# CCM0006.net
KiCad netlist of a schematic drawn in EAGLE
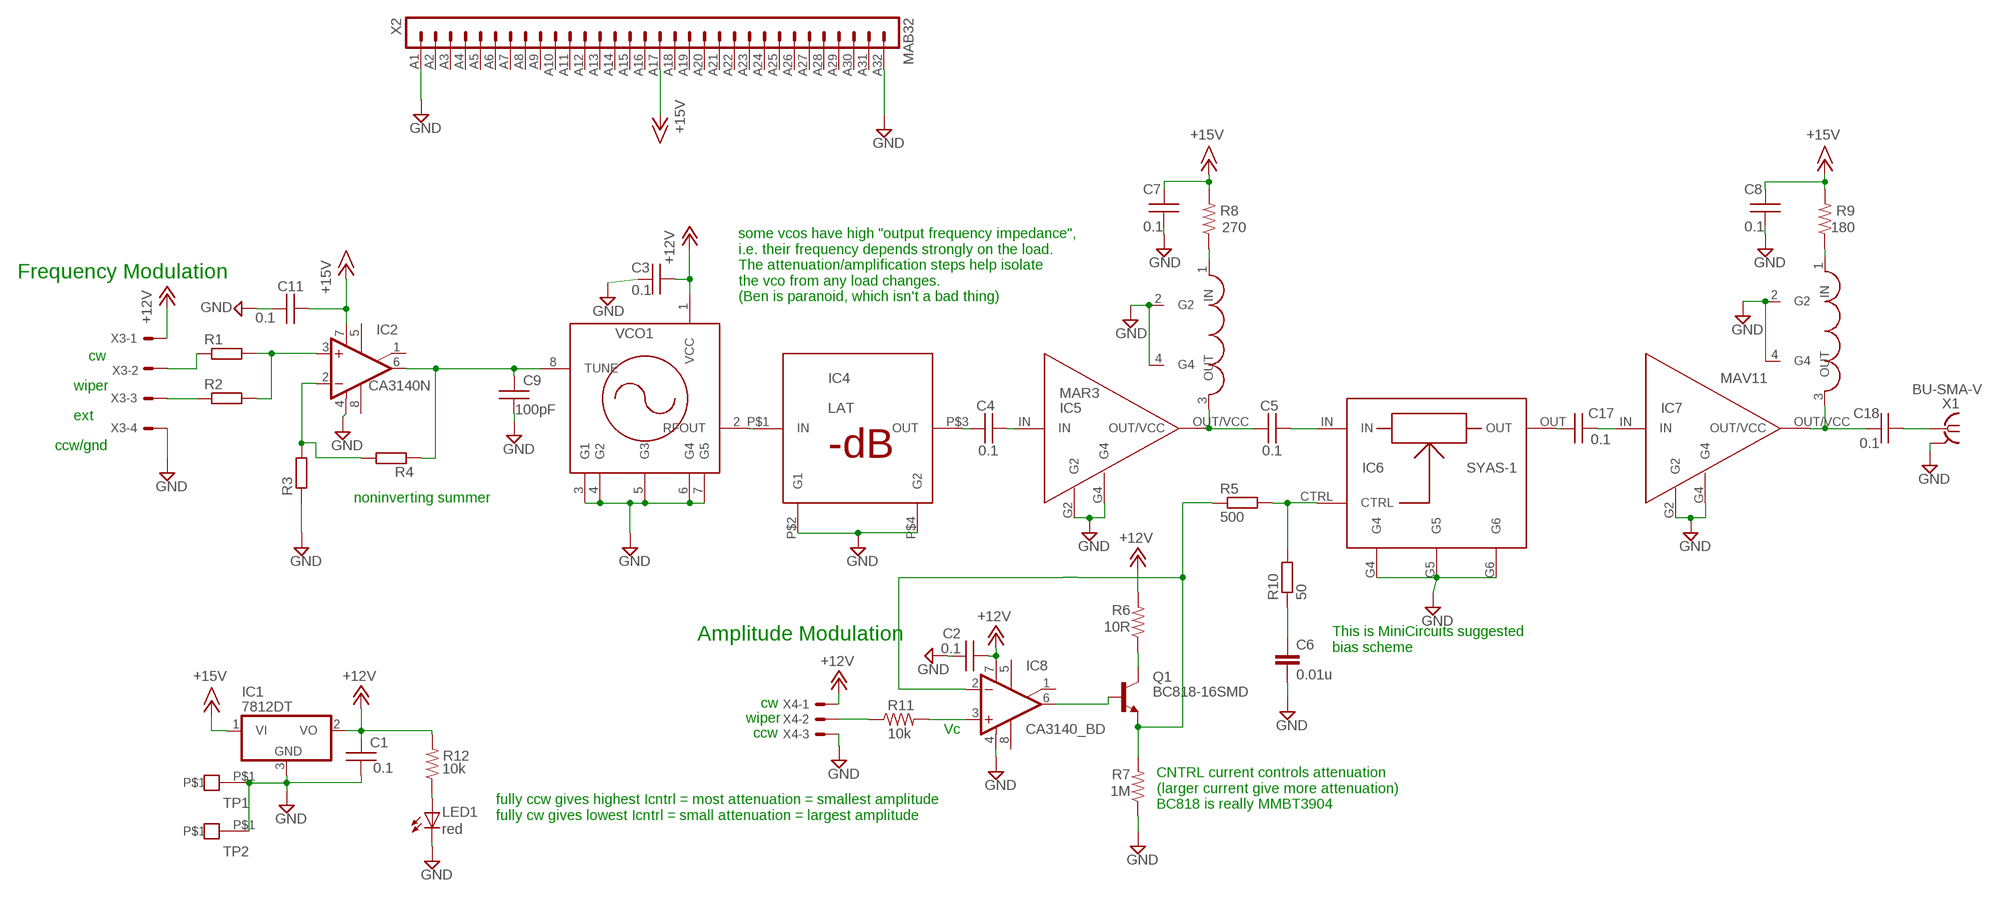
[diagram p0: schematic, sheet 1]

(export (version "E")
  (design (tool "Eeschema 10.0.6"))
  (components
    (comp (ref "C1")
      (value "0.1")
      (footprint "eagle-import:0805")
      (libsource (lib "eagle-import") (part "CAPACITOR0805"))
    )
    (comp (ref "C2")
      (value "0.1")
      (footprint "eagle-import:0805")
      (libsource (lib "eagle-import") (part "CAPACITOR0805"))
    )
    (comp (ref "C3")
      (value "0.1")
      (footprint "eagle-import:0805")
      (libsource (lib "eagle-import") (part "CAPACITOR0805"))
    )
    (comp (ref "C4")
      (value "0.1")
      (footprint "eagle-import:2010")
      (libsource (lib "eagle-import") (part "CAPACITOR2010"))
    )
    (comp (ref "C5")
      (value "0.1")
      (footprint "eagle-import:2010")
      (libsource (lib "eagle-import") (part "CAPACITOR2010"))
    )
    (comp (ref "C6")
      (value "0.01u")
      (footprint "eagle-import:C0805")
      (libsource (lib "eagle-import") (part "C-EUC0805"))
    )
    (comp (ref "C7")
      (value "0.1")
      (footprint "eagle-import:0805")
      (libsource (lib "eagle-import") (part "CAPACITOR0805"))
    )
    (comp (ref "C8")
      (value "0.1")
      (footprint "eagle-import:0603")
      (libsource (lib "eagle-import") (part "CAPACITOR0603"))
    )
    (comp (ref "C9")
      (value "100pF")
      (footprint "eagle-import:0805")
      (libsource (lib "eagle-import") (part "CAPACITOR0805"))
    )
    (comp (ref "C11")
      (value "0.1")
      (footprint "eagle-import:0805")
      (libsource (lib "eagle-import") (part "CAPACITOR0805"))
    )
    (comp (ref "C17")
      (value "0.1")
      (footprint "eagle-import:2010")
      (libsource (lib "eagle-import") (part "CAPACITOR2010"))
    )
    (comp (ref "C18")
      (value "0.1")
      (footprint "eagle-import:2010")
      (libsource (lib "eagle-import") (part "CAPACITOR2010"))
    )
    (comp (ref "IC1")
      (value "7812DT")
      (footprint "eagle-import:TO252")
      (libsource (lib "eagle-import") (part "78DT12"))
    )
    (comp (ref "IC2")
      (value "CA3140N")
      (footprint "eagle-import:DIL08")
      (libsource (lib "eagle-import") (part "CA3140N"))
    )
    (comp (ref "IC4")
      (value "LAT")
      (footprint "eagle-import:MMM168")
      (libsource (lib "eagle-import") (part "LAT"))
    )
    (comp (ref "IC5")
      (value "MAR3")
      (footprint "eagle-import:MAR")
      (libsource (lib "eagle-import") (part "MAR3"))
    )
    (comp (ref "IC6")
      (value "SYAS-1")
      (footprint "eagle-import:TTT166")
      (libsource (lib "eagle-import") (part "SYAS-1"))
    )
    (comp (ref "IC7")
      (value "MAV11")
      (footprint "eagle-import:MAR")
      (libsource (lib "eagle-import") (part "MAV11"))
    )
    (comp (ref "IC8")
      (value "CA3140_BD")
      (footprint "eagle-import:SO08")
      (libsource (lib "eagle-import") (part "CA3140_BD"))
    )
    (comp (ref "L1")
      (value "TCCH-80")
      (footprint "eagle-import:PL-147")
      (libsource (lib "eagle-import") (part "TCCH-80"))
    )
    (comp (ref "L2")
      (value "TCCH-80")
      (footprint "eagle-import:PL-147")
      (libsource (lib "eagle-import") (part "TCCH-80"))
    )
    (comp (ref "LED1")
      (value "red")
      (footprint "eagle-import:CHIPLED_0603")
      (libsource (lib "eagle-import") (part "LEDCHIPLED_0603"))
    )
    (comp (ref "Q1")
      (value "BC818-16SMD")
      (footprint "eagle-import:SOT23-BEC")
      (libsource (lib "eagle-import") (part "BC818SMD-16"))
    )
    (comp (ref "R1")
      (value "R-EU_0204/7")
      (footprint "eagle-import:0204_7")
      (libsource (lib "eagle-import") (part "R-EU_0204/7"))
    )
    (comp (ref "R2")
      (value "R-EU_0204/7")
      (footprint "eagle-import:0204_7")
      (libsource (lib "eagle-import") (part "R-EU_0204/7"))
    )
    (comp (ref "R3")
      (value "R-EU_0204/7")
      (footprint "eagle-import:0204_7")
      (libsource (lib "eagle-import") (part "R-EU_0204/7"))
    )
    (comp (ref "R4")
      (value "R-EU_0204/7")
      (footprint "eagle-import:0204_7")
      (libsource (lib "eagle-import") (part "R-EU_0204/7"))
    )
    (comp (ref "R5")
      (value "500")
      (footprint "eagle-import:R0805")
      (libsource (lib "eagle-import") (part "R-EU_R0805"))
    )
    (comp (ref "R6")
      (value "10R")
      (footprint "eagle-import:0805")
      (libsource (lib "eagle-import") (part "RESISTOR0805"))
    )
    (comp (ref "R7")
      (value "1M")
      (footprint "eagle-import:0805")
      (libsource (lib "eagle-import") (part "RESISTOR0805"))
    )
    (comp (ref "R8")
      (value "270")
      (footprint "eagle-import:2010")
      (libsource (lib "eagle-import") (part "RESISTOR2010"))
    )
    (comp (ref "R9")
      (value "180")
      (footprint "eagle-import:2010")
      (libsource (lib "eagle-import") (part "RESISTOR2010"))
    )
    (comp (ref "R10")
      (value "50")
      (footprint "eagle-import:R0805")
      (libsource (lib "eagle-import") (part "R-EU_R0805"))
    )
    (comp (ref "R11")
      (value "10k")
      (footprint "eagle-import:0805")
      (libsource (lib "eagle-import") (part "RESISTOR0805"))
    )
    (comp (ref "R12")
      (value "10k")
      (footprint "eagle-import:0805")
      (libsource (lib "eagle-import") (part "RESISTOR0805"))
    )
    (comp (ref "TP1")
      (value "TESTPOINT")
      (footprint "eagle-import:TESTPOINT")
      (libsource (lib "eagle-import") (part "TESTPOINT"))
    )
    (comp (ref "TP2")
      (value "TESTPOINT")
      (footprint "eagle-import:TESTPOINT")
      (libsource (lib "eagle-import") (part "TESTPOINT"))
    )
    (comp (ref "VCO1")
      (value "POSBIGPAD")
      (footprint "eagle-import:A01BIDPAD")
      (libsource (lib "eagle-import") (part "POSBIGPAD"))
    )
    (comp (ref "X1")
      (value "BU-SMA-V")
      (footprint "eagle-import:BU-SMA-V")
      (libsource (lib "eagle-import") (part "BU-SMA-V"))
    )
    (comp (ref "X2")
      (value "MAB32")
      (footprint "eagle-import:MAB32")
      (libsource (lib "eagle-import") (part "MAB32"))
    )
    (comp (ref "X3")
      (value "22-23-2041")
      (footprint "eagle-import:22-23-2041")
      (fields (field (name "MF") "MOLEX"))
      (libsource (lib "eagle-import") (part "22-23-2041"))
    )
    (comp (ref "X4")
      (value "22-23-2031")
      (footprint "eagle-import:22-23-2031")
      (fields (field (name "MF") "MOLEX"))
      (libsource (lib "eagle-import") (part "22-23-2031"))
    )
  )
  (nets
    (net (code "1") (name "+12V") (class "Default")
      (node (ref "C1") (pin "1") (pinfunction "1_1") (pintype "passive"))
      (node (ref "C2") (pin "2") (pinfunction "2_2") (pintype "passive"))
      (node (ref "C3") (pin "1") (pinfunction "1_1") (pintype "passive"))
      (node (ref "IC1") (pin "2") (pinfunction "VO_2") (pintype "passive"))
      (node (ref "IC8") (pin "7") (pinfunction "V+_7") (pintype "power_in"))
      (node (ref "R12") (pin "2") (pinfunction "2_2") (pintype "passive"))
      (node (ref "R6") (pin "2") (pinfunction "2_2") (pintype "passive"))
      (node (ref "VCO1") (pin "1") (pinfunction "VCC_1") (pintype "input"))
      (node (ref "X3") (pin "1") (pinfunction "S_1") (pintype "passive"))
      (node (ref "X4") (pin "1") (pinfunction "S_1") (pintype "passive"))
    )
    (net (code "2") (name "+15V") (class "Default")
      (node (ref "C11") (pin "2") (pinfunction "2_2") (pintype "passive"))
      (node (ref "C7") (pin "1") (pinfunction "1_1") (pintype "passive"))
      (node (ref "C8") (pin "1") (pinfunction "1_1") (pintype "passive"))
      (node (ref "IC1") (pin "1") (pinfunction "VI_1") (pintype "input"))
      (node (ref "IC2") (pin "7") (pinfunction "V+_7") (pintype "power_in"))
      (node (ref "R8") (pin "2") (pinfunction "2_2") (pintype "passive"))
      (node (ref "R9") (pin "2") (pinfunction "2_2") (pintype "passive"))
      (node (ref "X2") (pin "A17") (pinfunction "17_A17") (pintype "passive"))
    )
    (net (code "3") (name "GND") (class "Default")
      (node (ref "C1") (pin "2") (pinfunction "2_2") (pintype "passive"))
      (node (ref "C11") (pin "1") (pinfunction "1_1") (pintype "passive"))
      (node (ref "C2") (pin "1") (pinfunction "1_1") (pintype "passive"))
      (node (ref "C3") (pin "2") (pinfunction "2_2") (pintype "passive"))
      (node (ref "C6") (pin "2") (pinfunction "2_2") (pintype "passive"))
      (node (ref "C7") (pin "2") (pinfunction "2_2") (pintype "passive"))
      (node (ref "C8") (pin "2") (pinfunction "2_2") (pintype "passive"))
      (node (ref "C9") (pin "2") (pinfunction "2_2") (pintype "passive"))
      (node (ref "IC1") (pin "3") (pinfunction "GND_3") (pintype "passive"))
      (node (ref "IC2") (pin "4") (pinfunction "V-_4") (pintype "power_in"))
      (node (ref "IC4") (pin "P$2") (pinfunction "G1_P$2") (pintype "power_in"))
      (node (ref "IC4") (pin "P$4") (pinfunction "G2_P$4") (pintype "power_in"))
      (node (ref "IC5") (pin "G2") (pinfunction "G2_G2") (pintype "power_in"))
      (node (ref "IC5") (pin "G4") (pinfunction "G4_G4") (pintype "power_in"))
      (node (ref "IC6") (pin "G4") (pinfunction "G4_G4") (pintype "power_in"))
      (node (ref "IC6") (pin "G5") (pinfunction "G5_G5") (pintype "power_in"))
      (node (ref "IC6") (pin "G6") (pinfunction "G6_G6") (pintype "power_in"))
      (node (ref "IC7") (pin "G2") (pinfunction "G2_G2") (pintype "power_in"))
      (node (ref "IC7") (pin "G4") (pinfunction "G4_G4") (pintype "power_in"))
      (node (ref "IC8") (pin "4") (pinfunction "V-_4") (pintype "power_in"))
      (node (ref "L1") (pin "2") (pinfunction "G2_2") (pintype "power_in"))
      (node (ref "L1") (pin "4") (pinfunction "G4_4") (pintype "power_in"))
      (node (ref "L2") (pin "2") (pinfunction "G2_2") (pintype "power_in"))
      (node (ref "L2") (pin "4") (pinfunction "G4_4") (pintype "power_in"))
      (node (ref "LED1") (pin "C") (pinfunction "C_C") (pintype "passive"))
      (node (ref "R3") (pin "1") (pinfunction "1_1") (pintype "passive"))
      (node (ref "R7") (pin "1") (pinfunction "1_1") (pintype "passive"))
      (node (ref "TP1") (pin "P$1") (pinfunction "P$1_P$1") (pintype "bidirectional"))
      (node (ref "TP2") (pin "P$1") (pinfunction "P$1_P$1") (pintype "bidirectional"))
      (node (ref "VCO1") (pin "3") (pinfunction "G1_3") (pintype "power_in"))
      (node (ref "VCO1") (pin "4") (pinfunction "G2_4") (pintype "power_in"))
      (node (ref "VCO1") (pin "5") (pinfunction "G3_5") (pintype "power_in"))
      (node (ref "VCO1") (pin "6") (pinfunction "G4_6") (pintype "power_in"))
      (node (ref "VCO1") (pin "7") (pinfunction "G5_7") (pintype "power_in"))
      (node (ref "X1") (pin "2") (pinfunction "GND_2") (pintype "power_in"))
      (node (ref "X2") (pin "A1") (pinfunction "1_A1") (pintype "passive"))
      (node (ref "X2") (pin "A32") (pinfunction "32_A32") (pintype "passive"))
      (node (ref "X3") (pin "4") (pinfunction "S_4") (pintype "passive"))
      (node (ref "X4") (pin "3") (pinfunction "S_3") (pintype "passive"))
    )
    (net (code "4") (name "Net-(C4-Pad2)") (class "Default")
      (node (ref "C4") (pin "2") (pinfunction "2_2") (pintype "passive"))
      (node (ref "IC5") (pin "IN") (pinfunction "IN_IN") (pintype "input"))
    )
    (net (code "5") (name "Net-(C5-Pad2)") (class "Default")
      (node (ref "C5") (pin "2") (pinfunction "2_2") (pintype "passive"))
      (node (ref "IC6") (pin "IN") (pinfunction "IN_IN") (pintype "input"))
    )
    (net (code "6") (name "Net-(C6-Pad1)") (class "Default")
      (node (ref "C6") (pin "1") (pinfunction "1_1") (pintype "passive"))
      (node (ref "R10") (pin "1") (pinfunction "1_1") (pintype "passive"))
    )
    (net (code "7") (name "Net-(C17-Pad1)") (class "Default")
      (node (ref "C17") (pin "1") (pinfunction "1_1") (pintype "passive"))
      (node (ref "IC6") (pin "OUT") (pinfunction "OUT_OUT") (pintype "output"))
    )
    (net (code "8") (name "Net-(C17-Pad2)") (class "Default")
      (node (ref "C17") (pin "2") (pinfunction "2_2") (pintype "passive"))
      (node (ref "IC7") (pin "IN") (pinfunction "IN_IN") (pintype "input"))
    )
    (net (code "9") (name "Net-(C18-Pad2)") (class "Default")
      (node (ref "C18") (pin "2") (pinfunction "2_2") (pintype "passive"))
      (node (ref "X1") (pin "1") (pinfunction "1_1") (pintype "passive"))
    )
    (net (code "10") (name "Net-(IC2-+IN)") (class "Default")
      (node (ref "IC2") (pin "3") (pinfunction "+IN_3") (pintype "input"))
      (node (ref "R1") (pin "2") (pinfunction "2_2") (pintype "passive"))
      (node (ref "R2") (pin "2") (pinfunction "2_2") (pintype "passive"))
    )
    (net (code "11") (name "Net-(IC2--IN)") (class "Default")
      (node (ref "IC2") (pin "2") (pinfunction "-IN_2") (pintype "input"))
      (node (ref "R3") (pin "2") (pinfunction "2_2") (pintype "passive"))
      (node (ref "R4") (pin "2") (pinfunction "2_2") (pintype "passive"))
    )
    (net (code "12") (name "Net-(IC2-OUT)") (class "Default")
      (node (ref "C9") (pin "1") (pinfunction "1_1") (pintype "passive"))
      (node (ref "IC2") (pin "6") (pinfunction "OUT_6") (pintype "output"))
      (node (ref "R4") (pin "1") (pinfunction "1_1") (pintype "passive"))
      (node (ref "VCO1") (pin "8") (pinfunction "TUNE_8") (pintype "input"))
    )
    (net (code "13") (name "Net-(IC4-IN)") (class "Default")
      (node (ref "IC4") (pin "P$1") (pinfunction "IN_P$1") (pintype "input"))
      (node (ref "VCO1") (pin "2") (pinfunction "RFOUT_2") (pintype "output"))
    )
    (net (code "14") (name "Net-(IC4-OUT)") (class "Default")
      (node (ref "C4") (pin "1") (pinfunction "1_1") (pintype "passive"))
      (node (ref "IC4") (pin "P$3") (pinfunction "OUT_P$3") (pintype "output"))
    )
    (net (code "15") (name "Net-(IC6-PadCTRL)") (class "Default")
      (node (ref "IC6") (pin "CTRL") (pinfunction "CTRL_CTRL") (pintype "input"))
      (node (ref "R10") (pin "2") (pinfunction "2_2") (pintype "passive"))
      (node (ref "R5") (pin "2") (pinfunction "2_2") (pintype "passive"))
    )
    (net (code "16") (name "Net-(IC8-+IN)") (class "Default")
      (node (ref "IC8") (pin "3") (pinfunction "+IN_3") (pintype "input"))
      (node (ref "R11") (pin "2") (pinfunction "2_2") (pintype "passive"))
    )
    (net (code "17") (name "Net-(IC8--IN)") (class "Default")
      (node (ref "IC8") (pin "2") (pinfunction "-IN_2") (pintype "input"))
      (node (ref "Q1") (pin "E") (pinfunction "E_E") (pintype "passive"))
      (node (ref "R5") (pin "1") (pinfunction "1_1") (pintype "passive"))
      (node (ref "R7") (pin "2") (pinfunction "2_2") (pintype "passive"))
    )
    (net (code "18") (name "Net-(IC8-OUT)") (class "Default")
      (node (ref "IC8") (pin "6") (pinfunction "OUT_6") (pintype "output"))
      (node (ref "Q1") (pin "B") (pinfunction "B_B") (pintype "passive"))
    )
    (net (code "19") (name "Net-(L1-IN)") (class "Default")
      (node (ref "L1") (pin "1") (pinfunction "IN_1") (pintype "input"))
      (node (ref "R8") (pin "1") (pinfunction "1_1") (pintype "passive"))
    )
    (net (code "20") (name "Net-(L1-OUT)") (class "Default")
      (node (ref "C5") (pin "1") (pinfunction "1_1") (pintype "passive"))
      (node (ref "IC5") (pin "OUT/VCC") (pinfunction "OUT/VCC_OUT/VCC") (pintype "bidirectional"))
      (node (ref "L1") (pin "3") (pinfunction "OUT_3") (pintype "output"))
    )
    (net (code "21") (name "Net-(L2-IN)") (class "Default")
      (node (ref "L2") (pin "1") (pinfunction "IN_1") (pintype "input"))
      (node (ref "R9") (pin "1") (pinfunction "1_1") (pintype "passive"))
    )
    (net (code "22") (name "Net-(L2-OUT)") (class "Default")
      (node (ref "C18") (pin "1") (pinfunction "1_1") (pintype "passive"))
      (node (ref "IC7") (pin "OUT/VCC") (pinfunction "OUT/VCC_OUT/VCC") (pintype "bidirectional"))
      (node (ref "L2") (pin "3") (pinfunction "OUT_3") (pintype "output"))
    )
    (net (code "23") (name "Net-(LED1-PadA)") (class "Default")
      (node (ref "LED1") (pin "A") (pinfunction "A_A") (pintype "passive"))
      (node (ref "R12") (pin "1") (pinfunction "1_1") (pintype "passive"))
    )
    (net (code "24") (name "Net-(Q1-PadC)") (class "Default")
      (node (ref "Q1") (pin "C") (pinfunction "C_C") (pintype "passive"))
      (node (ref "R6") (pin "1") (pinfunction "1_1") (pintype "passive"))
    )
    (net (code "25") (name "Net-(X3B-S)") (class "Default")
      (node (ref "R1") (pin "1") (pinfunction "1_1") (pintype "passive"))
      (node (ref "X3") (pin "2") (pinfunction "S_2") (pintype "passive"))
    )
    (net (code "26") (name "Net-(X3C-S)") (class "Default")
      (node (ref "R2") (pin "1") (pinfunction "1_1") (pintype "passive"))
      (node (ref "X3") (pin "3") (pinfunction "S_3") (pintype "passive"))
    )
    (net (code "27") (name "Net-(X4B-S)") (class "Default")
      (node (ref "R11") (pin "1") (pinfunction "1_1") (pintype "passive"))
      (node (ref "X4") (pin "2") (pinfunction "S_2") (pintype "passive"))
    )
    (net (code "28") (name "unconnected-(IC2-CMP-Pad8)") (class "Default")
      (node (ref "IC2") (pin "8") (pinfunction "CMP_8") (pintype "passive"))
    )
    (net (code "29") (name "unconnected-(IC2-ON-Pad5)") (class "Default")
      (node (ref "IC2") (pin "5") (pinfunction "ON_5") (pintype "passive"))
    )
    (net (code "30") (name "unconnected-(IC2-ON{slash}CMP-Pad1)") (class "Default")
      (node (ref "IC2") (pin "1") (pinfunction "ON/CMP_1") (pintype "passive"))
    )
    (net (code "31") (name "unconnected-(IC8-CMP-Pad8)") (class "Default")
      (node (ref "IC8") (pin "8") (pinfunction "CMP_8") (pintype "passive"))
    )
    (net (code "32") (name "unconnected-(IC8-ON-Pad5)") (class "Default")
      (node (ref "IC8") (pin "5") (pinfunction "ON_5") (pintype "passive"))
    )
    (net (code "33") (name "unconnected-(IC8-ON{slash}CMP-Pad1)") (class "Default")
      (node (ref "IC8") (pin "1") (pinfunction "ON/CMP_1") (pintype "passive"))
    )
    (net (code "34") (name "unconnected-(X2-2-PadA2)") (class "Default")
      (node (ref "X2") (pin "A2") (pinfunction "2_A2") (pintype "passive"))
    )
    (net (code "35") (name "unconnected-(X2-3-PadA3)") (class "Default")
      (node (ref "X2") (pin "A3") (pinfunction "3_A3") (pintype "passive"))
    )
    (net (code "36") (name "unconnected-(X2-4-PadA4)") (class "Default")
      (node (ref "X2") (pin "A4") (pinfunction "4_A4") (pintype "passive"))
    )
    (net (code "37") (name "unconnected-(X2-5-PadA5)") (class "Default")
      (node (ref "X2") (pin "A5") (pinfunction "5_A5") (pintype "passive"))
    )
    (net (code "38") (name "unconnected-(X2-6-PadA6)") (class "Default")
      (node (ref "X2") (pin "A6") (pinfunction "6_A6") (pintype "passive"))
    )
    (net (code "39") (name "unconnected-(X2-7-PadA7)") (class "Default")
      (node (ref "X2") (pin "A7") (pinfunction "7_A7") (pintype "passive"))
    )
    (net (code "40") (name "unconnected-(X2-8-PadA8)") (class "Default")
      (node (ref "X2") (pin "A8") (pinfunction "8_A8") (pintype "passive"))
    )
    (net (code "41") (name "unconnected-(X2-9-PadA9)") (class "Default")
      (node (ref "X2") (pin "A9") (pinfunction "9_A9") (pintype "passive"))
    )
    (net (code "42") (name "unconnected-(X2-10-PadA10)") (class "Default")
      (node (ref "X2") (pin "A10") (pinfunction "10_A10") (pintype "passive"))
    )
    (net (code "43") (name "unconnected-(X2-11-PadA11)") (class "Default")
      (node (ref "X2") (pin "A11") (pinfunction "11_A11") (pintype "passive"))
    )
    (net (code "44") (name "unconnected-(X2-12-PadA12)") (class "Default")
      (node (ref "X2") (pin "A12") (pinfunction "12_A12") (pintype "passive"))
    )
    (net (code "45") (name "unconnected-(X2-13-PadA13)") (class "Default")
      (node (ref "X2") (pin "A13") (pinfunction "13_A13") (pintype "passive"))
    )
    (net (code "46") (name "unconnected-(X2-14-PadA14)") (class "Default")
      (node (ref "X2") (pin "A14") (pinfunction "14_A14") (pintype "passive"))
    )
    (net (code "47") (name "unconnected-(X2-15-PadA15)") (class "Default")
      (node (ref "X2") (pin "A15") (pinfunction "15_A15") (pintype "passive"))
    )
    (net (code "48") (name "unconnected-(X2-16-PadA16)") (class "Default")
      (node (ref "X2") (pin "A16") (pinfunction "16_A16") (pintype "passive"))
    )
    (net (code "49") (name "unconnected-(X2-18-PadA18)") (class "Default")
      (node (ref "X2") (pin "A18") (pinfunction "18_A18") (pintype "passive"))
    )
    (net (code "50") (name "unconnected-(X2-19-PadA19)") (class "Default")
      (node (ref "X2") (pin "A19") (pinfunction "19_A19") (pintype "passive"))
    )
    (net (code "51") (name "unconnected-(X2-20-PadA20)") (class "Default")
      (node (ref "X2") (pin "A20") (pinfunction "20_A20") (pintype "passive"))
    )
    (net (code "52") (name "unconnected-(X2-21-PadA21)") (class "Default")
      (node (ref "X2") (pin "A21") (pinfunction "21_A21") (pintype "passive"))
    )
    (net (code "53") (name "unconnected-(X2-22-PadA22)") (class "Default")
      (node (ref "X2") (pin "A22") (pinfunction "22_A22") (pintype "passive"))
    )
    (net (code "54") (name "unconnected-(X2-23-PadA23)") (class "Default")
      (node (ref "X2") (pin "A23") (pinfunction "23_A23") (pintype "passive"))
    )
    (net (code "55") (name "unconnected-(X2-24-PadA24)") (class "Default")
      (node (ref "X2") (pin "A24") (pinfunction "24_A24") (pintype "passive"))
    )
    (net (code "56") (name "unconnected-(X2-25-PadA25)") (class "Default")
      (node (ref "X2") (pin "A25") (pinfunction "25_A25") (pintype "passive"))
    )
    (net (code "57") (name "unconnected-(X2-26-PadA26)") (class "Default")
      (node (ref "X2") (pin "A26") (pinfunction "26_A26") (pintype "passive"))
    )
    (net (code "58") (name "unconnected-(X2-27-PadA27)") (class "Default")
      (node (ref "X2") (pin "A27") (pinfunction "27_A27") (pintype "passive"))
    )
    (net (code "59") (name "unconnected-(X2-28-PadA28)") (class "Default")
      (node (ref "X2") (pin "A28") (pinfunction "28_A28") (pintype "passive"))
    )
    (net (code "60") (name "unconnected-(X2-29-PadA29)") (class "Default")
      (node (ref "X2") (pin "A29") (pinfunction "29_A29") (pintype "passive"))
    )
    (net (code "61") (name "unconnected-(X2-30-PadA30)") (class "Default")
      (node (ref "X2") (pin "A30") (pinfunction "30_A30") (pintype "passive"))
    )
    (net (code "62") (name "unconnected-(X2-31-PadA31)") (class "Default")
      (node (ref "X2") (pin "A31") (pinfunction "31_A31") (pintype "passive"))
    )
  )
)
